# 2228_Recepteur_Alimentation.net
KiCad netlist of a schematic drawn in Altium Designer
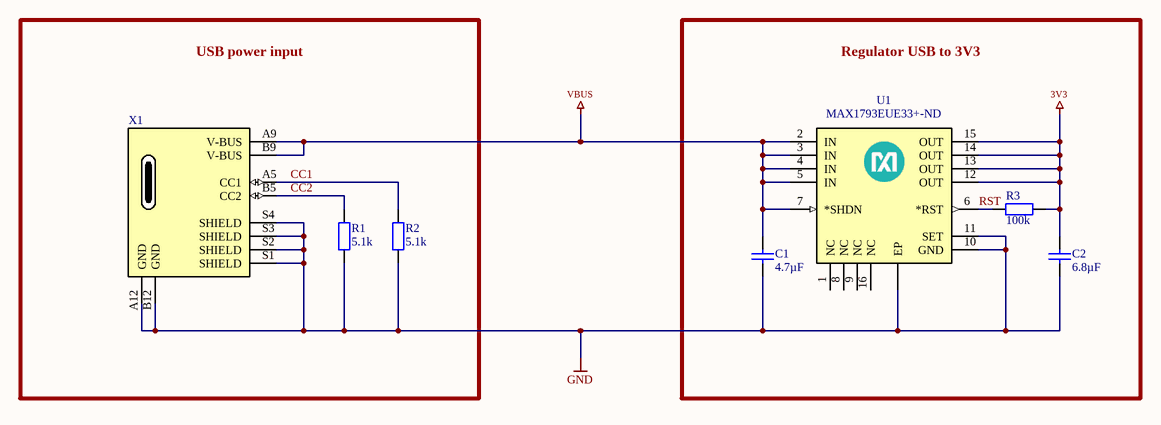
[diagram p0: 2228_Recepteur_Alimentation.SchDoc]

(export (version "E")
  (design (tool "Eeschema 10.0.6"))
  (components
    (comp (ref "C1")
      (value "4.7µF")
      (footprint "CAP_0805")
      (description "Ceramic capacitor")
      (fields (field (name "Comment") "CAP_SMD"))
      (libsource (lib "2228_AlarmeFenetre_Symbols") (part "CAP_SMD"))
    )
    (comp (ref "C2")
      (value "6.8µF")
      (footprint "CAP_0805")
      (description "Ceramic capacitor")
      (fields (field (name "Comment") "CAP_SMD"))
      (libsource (lib "2228_AlarmeFenetre_Symbols") (part "CAP_SMD"))
    )
    (comp (ref "R1")
      (value "5.1k")
      (footprint "RES_0805")
      (fields (field (name "Comment") "RES_SMD"))
      (libsource (lib "") (part "RES_SMD_1"))
    )
    (comp (ref "R2")
      (value "5.1k")
      (footprint "RES_0805")
      (fields (field (name "Comment") "RES_SMD"))
      (libsource (lib "") (part "RES_SMD_1"))
    )
    (comp (ref "R3")
      (value "100k")
      (footprint "RES_0805")
      (fields (field (name "Comment") "RES_SMD"))
      (libsource (lib "2228_AlarmeFenetre_Symbols") (part "RES_SMD"))
    )
    (comp (ref "U1")
      (value "MAX1793EUE33+")
      (footprint "2228_AlarmeFenetre_Footprints:SOP65P638X110-17N")
      (fields (field (name "SUPPLIER PART NUMBER 1") "MAX1793EUE33+-ND"))
      (libsource (lib "2228_AlarmeFenetre_Symbols") (part "MAX1793"))
    )
    (comp (ref "X1")
      (value "UJC-HP-3-SMT-TR")
      (footprint "2228_AlarmeFenetre_Footprints:CUI_UJC-HP-3-SMT-TR")
      (description "Type C, 3 A, Right Angle, Surface Mount (SMT), Power-Only USB Receptacle")
      (fields (field (name "MANUFACTURER") "CUI Devices"))
      (libsource (lib "2228_AlarmeFenetre_Symbols") (part "USB-C_CUI"))
    )
  )
  (nets
    (net (code "1") (name "/CC1") (class "Default")
      (node (ref "R2") (pin "2") (pinfunction "2_2") (pintype "passive"))
      (node (ref "X1") (pin "A5") (pinfunction "CC1_A5") (pintype "bidirectional"))
    )
    (net (code "2") (name "/CC2") (class "Default")
      (node (ref "R1") (pin "2") (pinfunction "2_2") (pintype "passive"))
      (node (ref "X1") (pin "B5") (pinfunction "CC2_B5") (pintype "bidirectional"))
    )
    (net (code "3") (name "/RST") (class "Default")
      (node (ref "R3") (pin "1") (pinfunction "1_1") (pintype "passive"))
      (node (ref "U1") (pin "6") (pinfunction "*RST_6") (pintype "output"))
    )
    (net (code "4") (name "3V3") (class "Default")
      (node (ref "C2") (pin "2") (pinfunction "2_2") (pintype "passive"))
      (node (ref "R3") (pin "2") (pinfunction "2_2") (pintype "passive"))
      (node (ref "U1") (pin "12") (pinfunction "OUT_12") (pintype "power_in"))
      (node (ref "U1") (pin "13") (pinfunction "OUT_13") (pintype "power_in"))
      (node (ref "U1") (pin "14") (pinfunction "OUT_14") (pintype "power_in"))
      (node (ref "U1") (pin "15") (pinfunction "OUT_15") (pintype "power_in"))
    )
    (net (code "5") (name "GND") (class "Default")
      (node (ref "C1") (pin "1") (pinfunction "1_1") (pintype "passive"))
      (node (ref "C2") (pin "1") (pinfunction "1_1") (pintype "passive"))
      (node (ref "R1") (pin "1") (pinfunction "1_1") (pintype "passive"))
      (node (ref "R2") (pin "1") (pinfunction "1_1") (pintype "passive"))
      (node (ref "U1") (pin "0") (pinfunction "EP_0") (pintype "passive"))
      (node (ref "U1") (pin "10") (pinfunction "GND_10") (pintype "power_in"))
      (node (ref "U1") (pin "11") (pinfunction "SET_11") (pintype "power_in"))
      (node (ref "X1") (pin "A12") (pinfunction "GND_A12") (pintype "power_in"))
      (node (ref "X1") (pin "B12") (pinfunction "GND_B12") (pintype "power_in"))
      (node (ref "X1") (pin "S1") (pinfunction "SHIELD_S1") (pintype "passive"))
      (node (ref "X1") (pin "S2") (pinfunction "SHIELD_S2") (pintype "passive"))
      (node (ref "X1") (pin "S3") (pinfunction "SHIELD_S3") (pintype "passive"))
      (node (ref "X1") (pin "S4") (pinfunction "SHIELD_S4") (pintype "passive"))
    )
    (net (code "6") (name "VBUS") (class "Default")
      (node (ref "C1") (pin "2") (pinfunction "2_2") (pintype "passive"))
      (node (ref "U1") (pin "2") (pinfunction "IN_2") (pintype "power_in"))
      (node (ref "U1") (pin "3") (pinfunction "IN_3") (pintype "power_in"))
      (node (ref "U1") (pin "4") (pinfunction "IN_4") (pintype "power_in"))
      (node (ref "U1") (pin "5") (pinfunction "IN_5") (pintype "power_in"))
      (node (ref "U1") (pin "7") (pinfunction "*SHDN_7") (pintype "input"))
      (node (ref "X1") (pin "A9") (pinfunction "V-BUS_A9") (pintype "power_in"))
      (node (ref "X1") (pin "B9") (pinfunction "V-BUS_B9") (pintype "power_in"))
    )
    (net (code "7") (name "unconnected-(U1-NC-Pad1)") (class "Default")
      (node (ref "U1") (pin "1") (pinfunction "NC_1") (pintype "passive"))
    )
    (net (code "8") (name "unconnected-(U1-NC-Pad8)") (class "Default")
      (node (ref "U1") (pin "8") (pinfunction "NC_8") (pintype "passive"))
    )
    (net (code "9") (name "unconnected-(U1-NC-Pad9)") (class "Default")
      (node (ref "U1") (pin "9") (pinfunction "NC_9") (pintype "passive"))
    )
    (net (code "10") (name "unconnected-(U1-NC-Pad16)") (class "Default")
      (node (ref "U1") (pin "16") (pinfunction "NC_16") (pintype "passive"))
    )
  )
)
